# AirU_PoE_V2.net
KiCad netlist of a schematic drawn in EAGLE
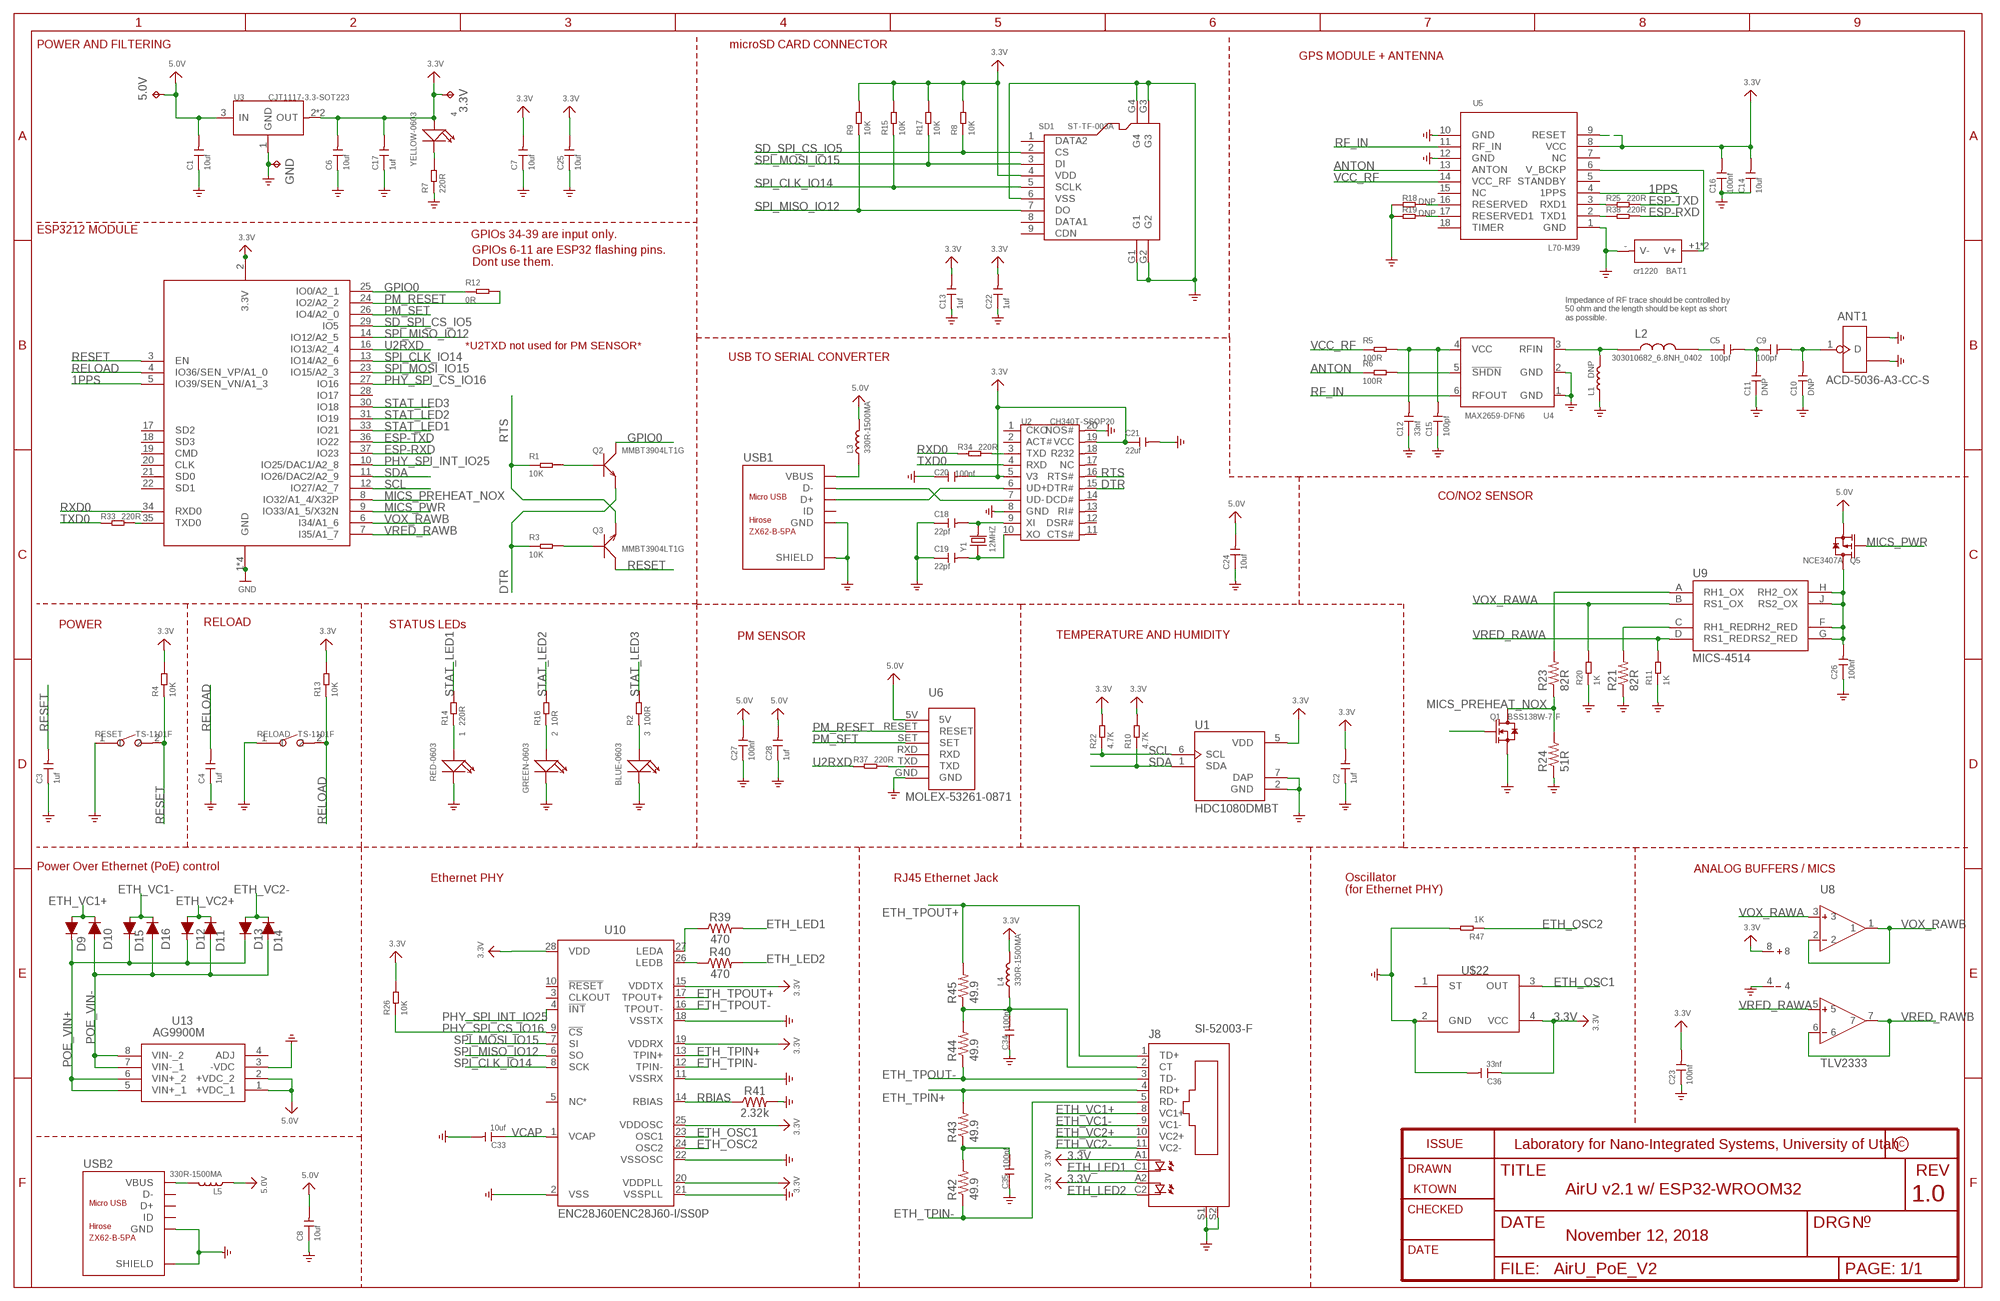
[diagram p0: schematic, sheet 1]

(export (version "E")
  (design (tool "Eeschema 10.0.6"))
  (components
    (comp (ref "1")
      (value "RED-0603")
      (footprint "eagle-import:LED-0603")
      (fields (field (name "MPN") "19-217-R6C-AL1M2VY-3T"))
      (libsource (lib "eagle-import") (part "LED-SMD-RED-DIFFUSED(0603)"))
    )
    (comp (ref "2")
      (value "GREEN-0603")
      (footprint "eagle-import:LED-0603")
      (fields (field (name "MPN") "19-217-G7C-AN1P2-3T"))
      (libsource (lib "eagle-import") (part "SMD-LED-CLEAR-GREEN(0603)"))
    )
    (comp (ref "3")
      (value "BLUE-0603")
      (footprint "eagle-import:LED-0603")
      (fields (field (name "MPN") "19-217-BHC-ZL1M2RY-3T"))
      (libsource (lib "eagle-import") (part "SMD-LED-CLEAR-BLUE(0603)"))
    )
    (comp (ref "3.3V")
      (value "TPTP20SQ")
      (footprint "eagle-import:TP20SQ")
      (libsource (lib "eagle-import") (part "TPTP20SQ"))
    )
    (comp (ref "4")
      (value "YELLOW-0603")
      (footprint "eagle-import:LED-0603")
      (fields (field (name "MPN") "19-217-Y5C-AM1N1VY-3T"))
      (libsource (lib "eagle-import") (part "SMD-LED-CLEAR-YELLOW(0603)"))
    )
    (comp (ref "5.0V")
      (value "TPTP20SQ")
      (footprint "eagle-import:TP20SQ")
      (libsource (lib "eagle-import") (part "TPTP20SQ"))
    )
    (comp (ref "ANT1")
      (value "ACD-5036-A3-CC-S")
      (footprint "eagle-import:ANT3-SMD-5.2X3.7X0.7MM")
      (libsource (lib "eagle-import") (part "ANTENNA-ACD5036"))
    )
    (comp (ref "BAT1")
      (value "cr1220")
      (footprint "eagle-import:BAT2P-13.5-CR1220")
      (libsource (lib "eagle-import") (part "DIP-BATTERY-CELL-HOLDER(1220)"))
    )
    (comp (ref "C1")
      (value "10uf")
      (footprint "eagle-import:C0603")
      (fields (field (name "MPN") "CC0603KRX5R6BB106"))
      (libsource (lib "eagle-import") (part "CERAMIC-10UF-10V-10%-X5R(0603)"))
    )
    (comp (ref "C2")
      (value "1uf")
      (footprint "eagle-import:C0603")
      (fields (field (name "MPN") "CC0603KRX7R8BB105"))
      (libsource (lib "eagle-import") (part "CERAMIC-1UF-25V-10%-X7R(0603)"))
    )
    (comp (ref "C3")
      (value "1uf")
      (footprint "eagle-import:C0603")
      (fields (field (name "MPN") "CC0603KRX7R8BB105"))
      (libsource (lib "eagle-import") (part "CERAMIC-1UF-25V-10%-X7R(0603)"))
    )
    (comp (ref "C4")
      (value "1uf")
      (footprint "eagle-import:C0603")
      (fields (field (name "MPN") "CC0603KRX7R8BB105"))
      (libsource (lib "eagle-import") (part "CERAMIC-1UF-25V-10%-X7R(0603)"))
    )
    (comp (ref "C5")
      (value "100pf")
      (footprint "eagle-import:C0603")
      (fields (field (name "MPN") "CC0603JRNPO9BN101"))
      (libsource (lib "eagle-import") (part "CERAMIC-100PF-50V-5%-NPO(0603)"))
    )
    (comp (ref "C6")
      (value "10uf")
      (footprint "eagle-import:C0603")
      (fields (field (name "MPN") "CC0603KRX5R6BB106"))
      (libsource (lib "eagle-import") (part "CERAMIC-10UF-10V-10%-X5R(0603)"))
    )
    (comp (ref "C7")
      (value "10uf")
      (footprint "eagle-import:C0603")
      (fields (field (name "MPN") "CC0603KRX5R6BB106"))
      (libsource (lib "eagle-import") (part "CERAMIC-10UF-10V-10%-X5R(0603)"))
    )
    (comp (ref "C8")
      (value "10uf")
      (footprint "eagle-import:C0603")
      (fields (field (name "MPN") "CC0603KRX5R6BB106"))
      (libsource (lib "eagle-import") (part "CERAMIC-10UF-10V-10%-X5R(0603)"))
    )
    (comp (ref "C9")
      (value "100pf")
      (footprint "eagle-import:C0603")
      (fields (field (name "MPN") "CC0603JRNPO9BN101"))
      (libsource (lib "eagle-import") (part "CERAMIC-100PF-50V-5%-NPO(0603)"))
    )
    (comp (ref "C10")
      (value "DNP")
      (footprint "eagle-import:C0603")
      (fields (field (name "MPN") "CC0603JRNPO9BN101"))
      (libsource (lib "eagle-import") (part "CERAMIC-100PF-50V-5%-NPO(0603)"))
    )
    (comp (ref "C11")
      (value "DNP")
      (footprint "eagle-import:C0603")
      (fields (field (name "MPN") "CC0603JRNPO9BN101"))
      (libsource (lib "eagle-import") (part "CERAMIC-100PF-50V-5%-NPO(0603)"))
    )
    (comp (ref "C12")
      (value "33nf")
      (footprint "eagle-import:C0603")
      (fields (field (name "MPN") "CC0603KRX7R9BB333"))
      (libsource (lib "eagle-import") (part "CERAMIC-33NF-50V-10%-X7R(0603)"))
    )
    (comp (ref "C13")
      (value "1uf")
      (footprint "eagle-import:C0603")
      (fields (field (name "MPN") "CC0603KRX7R8BB105"))
      (libsource (lib "eagle-import") (part "CERAMIC-1UF-25V-10%-X7R(0603)"))
    )
    (comp (ref "C14")
      (value "10uf")
      (footprint "eagle-import:C0603")
      (fields (field (name "MPN") "CC0603KRX5R6BB106"))
      (libsource (lib "eagle-import") (part "CERAMIC-10UF-10V-10%-X5R(0603)"))
    )
    (comp (ref "C15")
      (value "100pf")
      (footprint "eagle-import:C0603")
      (fields (field (name "MPN") "CC0603JRNPO9BN101"))
      (libsource (lib "eagle-import") (part "CERAMIC-100PF-50V-5%-NPO(0603)"))
    )
    (comp (ref "C16")
      (value "100nf")
      (footprint "eagle-import:C0603")
      (fields (field (name "MPN") "CC0603KRX7R9BB104"))
      (libsource (lib "eagle-import") (part "CERAMIC-100NF-50V-10%-X7R(0603)"))
    )
    (comp (ref "C17")
      (value "1uf")
      (footprint "eagle-import:C0603")
      (fields (field (name "MPN") "CC0603KRX7R8BB105"))
      (libsource (lib "eagle-import") (part "CERAMIC-1UF-25V-10%-X7R(0603)"))
    )
    (comp (ref "C18")
      (value "22pf")
      (footprint "eagle-import:C0603")
      (fields (field (name "MPN") "CC0603JRNPO9BN220"))
      (libsource (lib "eagle-import") (part "CERAMIC-22PF-50V-5%-NPO(0603)"))
    )
    (comp (ref "C19")
      (value "22pf")
      (footprint "eagle-import:C0603")
      (fields (field (name "MPN") "CC0603JRNPO9BN220"))
      (libsource (lib "eagle-import") (part "CERAMIC-22PF-50V-5%-NPO(0603)"))
    )
    (comp (ref "C20")
      (value "100nf")
      (footprint "eagle-import:C0603")
      (fields (field (name "MPN") "CC0603KRX7R9BB104"))
      (libsource (lib "eagle-import") (part "CERAMIC-100NF-50V-10%-X7R(0603)"))
    )
    (comp (ref "C21")
      (value "22uf")
      (footprint "eagle-import:C0805")
      (fields (field (name "MPN") "CC0805MKX5R5BB226"))
      (libsource (lib "eagle-import") (part "CERAMIC-22UF-6.3V-20%-X5R(0805)"))
    )
    (comp (ref "C22")
      (value "1uf")
      (footprint "eagle-import:C0603")
      (fields (field (name "MPN") "CC0603KRX7R8BB105"))
      (libsource (lib "eagle-import") (part "CERAMIC-1UF-25V-10%-X7R(0603)"))
    )
    (comp (ref "C23")
      (value "100nf")
      (footprint "eagle-import:C0603")
      (fields (field (name "MPN") "CC0603KRX7R9BB104"))
      (libsource (lib "eagle-import") (part "CERAMIC-100NF-50V-10%-X7R(0603)"))
    )
    (comp (ref "C24")
      (value "10uf")
      (footprint "eagle-import:C0603")
      (fields (field (name "MPN") "CC0603KRX5R6BB106"))
      (libsource (lib "eagle-import") (part "CERAMIC-10UF-10V-10%-X5R(0603)"))
    )
    (comp (ref "C25")
      (value "10uf")
      (footprint "eagle-import:C0603")
      (fields (field (name "MPN") "CC0603KRX5R6BB106"))
      (libsource (lib "eagle-import") (part "CERAMIC-10UF-10V-10%-X5R(0603)"))
    )
    (comp (ref "C26")
      (value "100nf")
      (footprint "eagle-import:C0603")
      (fields (field (name "MPN") "CC0603KRX7R9BB104"))
      (libsource (lib "eagle-import") (part "CERAMIC-100NF-50V-10%-X7R(0603)"))
    )
    (comp (ref "C27")
      (value "100nf")
      (footprint "eagle-import:C0603")
      (fields (field (name "MPN") "CC0603KRX7R9BB104"))
      (libsource (lib "eagle-import") (part "CERAMIC-100NF-50V-10%-X7R(0603)"))
    )
    (comp (ref "C28")
      (value "1uf")
      (footprint "eagle-import:C0603")
      (fields (field (name "MPN") "CC0603KRX7R8BB105"))
      (libsource (lib "eagle-import") (part "CERAMIC-1UF-25V-10%-X7R(0603)"))
    )
    (comp (ref "C33")
      (value "10uf")
      (footprint "eagle-import:C0603")
      (fields (field (name "MPN") "CC0603KRX5R6BB106"))
      (libsource (lib "eagle-import") (part "CERAMIC-10UF-10V-10%-X5R(0603)"))
    )
    (comp (ref "C34")
      (value "100nf")
      (footprint "eagle-import:C0603")
      (fields (field (name "MPN") "CC0603KRX7R9BB104"))
      (libsource (lib "eagle-import") (part "CERAMIC-100NF-50V-10%-X7R(0603)"))
    )
    (comp (ref "C35")
      (value "100nf")
      (footprint "eagle-import:C0603")
      (fields (field (name "MPN") "CC0603KRX7R9BB104"))
      (libsource (lib "eagle-import") (part "CERAMIC-100NF-50V-10%-X7R(0603)"))
    )
    (comp (ref "C36")
      (value "33nf")
      (footprint "eagle-import:C0603")
      (fields (field (name "MPN") "CC0603KRX7R9BB333"))
      (libsource (lib "eagle-import") (part "CERAMIC-33NF-50V-10%-X7R(0603)"))
    )
    (comp (ref "D9")
      (value "250mA/100V")
      (footprint "eagle-import:SOD-323")
      (libsource (lib "eagle-import") (part "DIODE-BAS16J"))
    )
    (comp (ref "D10")
      (value "250mA/100V")
      (footprint "eagle-import:SOD-323")
      (libsource (lib "eagle-import") (part "DIODE-BAS16J"))
    )
    (comp (ref "D11")
      (value "250mA/100V")
      (footprint "eagle-import:SOD-323")
      (libsource (lib "eagle-import") (part "DIODE-BAS16J"))
    )
    (comp (ref "D12")
      (value "250mA/100V")
      (footprint "eagle-import:SOD-323")
      (libsource (lib "eagle-import") (part "DIODE-BAS16J"))
    )
    (comp (ref "D13")
      (value "250mA/100V")
      (footprint "eagle-import:SOD-323")
      (libsource (lib "eagle-import") (part "DIODE-BAS16J"))
    )
    (comp (ref "D14")
      (value "250mA/100V")
      (footprint "eagle-import:SOD-323")
      (libsource (lib "eagle-import") (part "DIODE-BAS16J"))
    )
    (comp (ref "D15")
      (value "250mA/100V")
      (footprint "eagle-import:SOD-323")
      (libsource (lib "eagle-import") (part "DIODE-BAS16J"))
    )
    (comp (ref "D16")
      (value "250mA/100V")
      (footprint "eagle-import:SOD-323")
      (libsource (lib "eagle-import") (part "DIODE-BAS16J"))
    )
    (comp (ref "GND")
      (value "TPTP20SQ")
      (footprint "eagle-import:TP20SQ")
      (libsource (lib "eagle-import") (part "TPTP20SQ"))
    )
    (comp (ref "J8")
      (value "SI-52003-F")
      (footprint "eagle-import:SI-52003-F")
      (fields (field (name "MF") "Stewart Connector"))
      (libsource (lib "eagle-import") (part "SI-52003-F"))
    )
    (comp (ref "L1")
      (value "DNP")
      (footprint "eagle-import:L0201")
      (libsource (lib "eagle-import") (part "INDUCTOR/FERRITE-BEAD-0201"))
    )
    (comp (ref "L2")
      (value "303010682_6.8NH_0402")
      (footprint "eagle-import:L0402")
      (libsource (lib "eagle-import") (part "303010682_6.8NH_0402"))
    )
    (comp (ref "L3")
      (value "330R-1500MA")
      (footprint "eagle-import:L0805")
      (fields (field (name "MPN") "BLM21PG331SN1D"))
      (libsource (lib "eagle-import") (part "SMD-FERRITE-BEAD-330R-1500MA(0805)'0805'"))
    )
    (comp (ref "L4")
      (value "330R-1500MA")
      (footprint "eagle-import:L0805")
      (fields (field (name "MPN") "BLM21PG331SN1D"))
      (libsource (lib "eagle-import") (part "SMD-FERRITE-BEAD-330R-1500MA(0805)'0805'"))
    )
    (comp (ref "L5")
      (value "330R-1500MA")
      (footprint "eagle-import:L0805")
      (fields (field (name "MPN") "BLM21PG331SN1D"))
      (libsource (lib "eagle-import") (part "SMD-FERRITE-BEAD-330R-1500MA(0805)'0805'"))
    )
    (comp (ref "Q1")
      (value "BSS138W-7-F")
      (footprint "eagle-import:SOT-23")
      (libsource (lib "eagle-import") (part "SMD-MOSFET-N-CH-50V-200MA-BSS138W-7-F(SOT-23)"))
    )
    (comp (ref "Q2")
      (value "MMBT3904LT1G")
      (footprint "eagle-import:SOT-23")
      (libsource (lib "eagle-import") (part "SMD-TRANSISTORS-NPN-40V-200MA-MMBT3904LT1G(SOT-23)"))
    )
    (comp (ref "Q3")
      (value "MMBT3904LT1G")
      (footprint "eagle-import:SOT-23")
      (libsource (lib "eagle-import") (part "SMD-TRANSISTORS-NPN-40V-200MA-MMBT3904LT1G(SOT-23)"))
    )
    (comp (ref "Q5")
      (value "NCE3407A")
      (footprint "eagle-import:SOT-23")
      (libsource (lib "eagle-import") (part "SMD-MOSFET-P-CH-VDC=30V-ID=4.3A-NCE3407A(SOT-23)"))
    )
    (comp (ref "R1")
      (value "10K")
      (footprint "eagle-import:R0603")
      (fields (field (name "MPN") "RC0603FR-0710KL"))
      (libsource (lib "eagle-import") (part "SMD-RES-10K-1%-1/10W(0603)"))
    )
    (comp (ref "R2")
      (value "100R")
      (footprint "eagle-import:R0603")
      (fields (field (name "MPN") "RC0603JR-07100RL"))
      (libsource (lib "eagle-import") (part "SMD-RES-100R-5%-1/10W(0603)"))
    )
    (comp (ref "R3")
      (value "10K")
      (footprint "eagle-import:R0603")
      (fields (field (name "MPN") "RC0603FR-0710KL"))
      (libsource (lib "eagle-import") (part "SMD-RES-10K-1%-1/10W(0603)"))
    )
    (comp (ref "R4")
      (value "10K")
      (footprint "eagle-import:R0603")
      (fields (field (name "MPN") "RC0603FR-0710KL"))
      (libsource (lib "eagle-import") (part "SMD-RES-10K-1%-1/10W(0603)"))
    )
    (comp (ref "R5")
      (value "100R")
      (footprint "eagle-import:R0603")
      (fields (field (name "MPN") "RC0603JR-07100RL"))
      (libsource (lib "eagle-import") (part "SMD-RES-100R-5%-1/10W(0603)"))
    )
    (comp (ref "R6")
      (value "100R")
      (footprint "eagle-import:R0603")
      (fields (field (name "MPN") "RC0603JR-07100RL"))
      (libsource (lib "eagle-import") (part "SMD-RES-100R-5%-1/10W(0603)"))
    )
    (comp (ref "R7")
      (value "220R")
      (footprint "eagle-import:R0603")
      (fields (field (name "MPN") "RC0603JR-07220RL"))
      (libsource (lib "eagle-import") (part "SMD-RES-220R-5%-1/10W(0603)"))
    )
    (comp (ref "R8")
      (value "10K")
      (footprint "eagle-import:R0603")
      (fields (field (name "MPN") "RC0603FR-0710KL"))
      (libsource (lib "eagle-import") (part "SMD-RES-10K-1%-1/10W(0603)"))
    )
    (comp (ref "R9")
      (value "10K")
      (footprint "eagle-import:R0603")
      (fields (field (name "MPN") "RC0603FR-0710KL"))
      (libsource (lib "eagle-import") (part "SMD-RES-10K-1%-1/10W(0603)"))
    )
    (comp (ref "R10")
      (value "4.7K")
      (footprint "eagle-import:R0603")
      (fields (field (name "MPN") "RC0603JR-074K7L"))
      (libsource (lib "eagle-import") (part "SMD-RES-4.7K-5%-1/10W(0603)"))
    )
    (comp (ref "R11")
      (value "1K")
      (footprint "eagle-import:R0603")
      (fields (field (name "MPN") "RC0603FR-071KL"))
      (libsource (lib "eagle-import") (part "SMD-RES-1K-1%-1/10W(0603)"))
    )
    (comp (ref "R12")
      (value "0R")
      (footprint "eagle-import:R0603")
      (fields (field (name "MPN") "RC0603JR-070RL"))
      (libsource (lib "eagle-import") (part "SMD-RES-0R-5%-1/10W(0603)"))
    )
    (comp (ref "R13")
      (value "10K")
      (footprint "eagle-import:R0603")
      (fields (field (name "MPN") "RC0603FR-0710KL"))
      (libsource (lib "eagle-import") (part "SMD-RES-10K-1%-1/10W(0603)"))
    )
    (comp (ref "R14")
      (value "220R")
      (footprint "eagle-import:R0603")
      (fields (field (name "MPN") "RC0603JR-07220RL"))
      (libsource (lib "eagle-import") (part "SMD-RES-220R-5%-1/10W(0603)"))
    )
    (comp (ref "R15")
      (value "10K")
      (footprint "eagle-import:R0603")
      (fields (field (name "MPN") "RC0603FR-0710KL"))
      (libsource (lib "eagle-import") (part "SMD-RES-10K-1%-1/10W(0603)"))
    )
    (comp (ref "R16")
      (value "10R")
      (footprint "eagle-import:R0603")
      (fields (field (name "MPN") "RC0603JR-0710RL"))
      (libsource (lib "eagle-import") (part "SMD-RES-10R-5%-1/10W(0603)"))
    )
    (comp (ref "R17")
      (value "10K")
      (footprint "eagle-import:R0603")
      (fields (field (name "MPN") "RC0603FR-0710KL"))
      (libsource (lib "eagle-import") (part "SMD-RES-10K-1%-1/10W(0603)"))
    )
    (comp (ref "R18")
      (value "DNP")
      (footprint "eagle-import:R0603")
      (fields (field (name "MPN") "RC0603FR-0710KL"))
      (libsource (lib "eagle-import") (part "SMD-RES-10K-1%-1/10W(0603)"))
    )
    (comp (ref "R19")
      (value "DNP")
      (footprint "eagle-import:R0603")
      (fields (field (name "MPN") "RC0603FR-0710KL"))
      (libsource (lib "eagle-import") (part "SMD-RES-10K-1%-1/10W(0603)"))
    )
    (comp (ref "R20")
      (value "1K")
      (footprint "eagle-import:R0603")
      (fields (field (name "MPN") "RC0603FR-071KL"))
      (libsource (lib "eagle-import") (part "SMD-RES-1K-1%-1/10W(0603)"))
    )
    (comp (ref "R21")
      (value "82R")
      (footprint "eagle-import:R0603")
      (libsource (lib "eagle-import") (part "rcl_334_R-US_R0603"))
    )
    (comp (ref "R22")
      (value "4.7K")
      (footprint "eagle-import:R0603")
      (fields (field (name "MPN") "RC0603JR-074K7L"))
      (libsource (lib "eagle-import") (part "SMD-RES-4.7K-5%-1/10W(0603)"))
    )
    (comp (ref "R23")
      (value "82R")
      (footprint "eagle-import:R0603")
      (libsource (lib "eagle-import") (part "rcl_334_R-US_R0603"))
    )
    (comp (ref "R24")
      (value "51R")
      (footprint "eagle-import:R0603")
      (libsource (lib "eagle-import") (part "rcl_334_R-US_R0603"))
    )
    (comp (ref "R25")
      (value "220R")
      (footprint "eagle-import:R0603")
      (fields (field (name "MPN") "RC0603JR-07220RL"))
      (libsource (lib "eagle-import") (part "SMD-RES-220R-5%-1/10W(0603)"))
    )
    (comp (ref "R26")
      (value "10K")
      (footprint "eagle-import:R0603")
      (fields (field (name "MPN") "RC0603FR-0710KL"))
      (libsource (lib "eagle-import") (part "SMD-RES-10K-1%-1/10W(0603)"))
    )
    (comp (ref "R33")
      (value "220R")
      (footprint "eagle-import:R0603")
      (fields (field (name "MPN") "RC0603JR-07220RL"))
      (libsource (lib "eagle-import") (part "SMD-RES-220R-5%-1/10W(0603)"))
    )
    (comp (ref "R34")
      (value "220R")
      (footprint "eagle-import:R0603")
      (fields (field (name "MPN") "RC0603JR-07220RL"))
      (libsource (lib "eagle-import") (part "SMD-RES-220R-5%-1/10W(0603)"))
    )
    (comp (ref "R37")
      (value "220R")
      (footprint "eagle-import:R0603")
      (fields (field (name "MPN") "RC0603JR-07220RL"))
      (libsource (lib "eagle-import") (part "SMD-RES-220R-5%-1/10W(0603)"))
    )
    (comp (ref "R38")
      (value "220R")
      (footprint "eagle-import:R0603")
      (fields (field (name "MPN") "RC0603JR-07220RL"))
      (libsource (lib "eagle-import") (part "SMD-RES-220R-5%-1/10W(0603)"))
    )
    (comp (ref "R39")
      (value "470")
      (footprint "eagle-import:0603")
      (libsource (lib "eagle-import") (part "470OHM-0603-1/10W-1%"))
    )
    (comp (ref "R40")
      (value "470")
      (footprint "eagle-import:0603")
      (libsource (lib "eagle-import") (part "470OHM-0603-1/10W-1%"))
    )
    (comp (ref "R41")
      (value "2.32k")
      (footprint "eagle-import:0603")
      (libsource (lib "eagle-import") (part "2.2KOHM-0603-1/10W-1%"))
    )
    (comp (ref "R42")
      (value "49.9")
      (footprint "eagle-import:M0805")
      (libsource (lib "eagle-import") (part "R-US_M0805"))
    )
    (comp (ref "R43")
      (value "49.9")
      (footprint "eagle-import:M0805")
      (libsource (lib "eagle-import") (part "R-US_M0805"))
    )
    (comp (ref "R44")
      (value "49.9")
      (footprint "eagle-import:M0805")
      (libsource (lib "eagle-import") (part "R-US_M0805"))
    )
    (comp (ref "R45")
      (value "49.9")
      (footprint "eagle-import:M0805")
      (libsource (lib "eagle-import") (part "R-US_M0805"))
    )
    (comp (ref "R47")
      (value "1K")
      (footprint "eagle-import:R0603")
      (fields (field (name "MPN") "RC0603FR-071KL"))
      (libsource (lib "eagle-import") (part "SMD-RES-1K-1%-1/10W(0603)"))
    )
    (comp (ref "RELOAD")
      (value "TS-1101F")
      (footprint "eagle-import:SW2-5.0-6.0X3.0X4.3MM")
      (libsource (lib "eagle-import") (part "DIP-BUTTON(2P-6.0X3.0X4.3MM)-TS-1101F"))
    )
    (comp (ref "RESET")
      (value "TS-1101F")
      (footprint "eagle-import:SW2-5.0-6.0X3.0X4.3MM")
      (libsource (lib "eagle-import") (part "DIP-BUTTON(2P-6.0X3.0X4.3MM)-TS-1101F"))
    )
    (comp (ref "SD1")
      (value "ST-TF-003A")
      (footprint "eagle-import:MICRO-SD9+4P-SMD-16.1X14.5X1.85MM")
      (libsource (lib "eagle-import") (part "MICRO-SD-CARD-SOCKET-9P(ST-TF-003A)"))
    )
    (comp (ref "U$22")
      (value "SPXO25MHZ7050-4P")
      (footprint "eagle-import:DFN700X500X150-4N")
      (libsource (lib "eagle-import") (part "SPXO25MHZ7050-4P"))
    )
    (comp (ref "U1")
      (value "HDC1080DMBT")
      (footprint "eagle-import:SON100P300X300X80-7N")
      (fields (field (name "DIGI-KEY_PART_NUMBER") "296-43864-1-ND") (field (name "MF") "Texas Instruments"))
      (libsource (lib "eagle-import") (part "HDC1080DMBT"))
    )
    (comp (ref "U2")
      (value "CH340T-SSOP20")
      (footprint "eagle-import:SSOP20-0.65-7.6X5.2MM")
      (fields (field (name "MPN") "CH340T"))
      (libsource (lib "eagle-import") (part "INTERFACE-CH340T(SSOP20)"))
    )
    (comp (ref "U3")
      (value "CJT1117-3.3-SOT223")
      (footprint "eagle-import:SOT-223")
      (fields (field (name "MPN") "CJT1117-3.3"))
      (libsource (lib "eagle-import") (part "PMIC-CJT1117-3.3(SOT223)"))
    )
    (comp (ref "U4")
      (value "MAX2659-DFN6")
      (footprint "eagle-import:DFN6-0.5-1.5X1.2X0.72MM")
      (fields (field (name "MPN") "MAX2659"))
      (libsource (lib "eagle-import") (part "AMPLIFIER-MAX2659"))
    )
    (comp (ref "U5")
      (value "L70-M39")
      (footprint "eagle-import:LGA18-1.1-9.7X10.1X2.5MM")
      (fields (field (name "MPN") "L70"))
      (libsource (lib "eagle-import") (part "MOUDLE-GPS-L70-HARDWARE"))
    )
    (comp (ref "U6")
      (value "MOLEX-53261-0871")
      (footprint "eagle-import:MOLEX-53261-0871")
      (libsource (lib "eagle-import") (part "MOLEX-53261-0871"))
    )
    (comp (ref "U7")
      (value "ESP32_WROOM32_SKINNY")
      (footprint "eagle-import:WROOM32_SKINNY")
      (libsource (lib "eagle-import") (part "ESP32_WROOM32_SKINNY"))
    )
    (comp (ref "U8")
      (value "TLV2333")
      (footprint "eagle-import:TLV2333")
      (libsource (lib "eagle-import") (part "TLV2333"))
    )
    (comp (ref "U9")
      (value "MICS-4514")
      (footprint "eagle-import:MICS_10-SMD")
      (fields (field (name "MF") "Amphenol"))
      (libsource (lib "eagle-import") (part "MICS-4514"))
    )
    (comp (ref "U10")
      (value "ENC28J60ENC28J60-I/SS0P")
      (footprint "eagle-import:SOP65P780X200-28")
      (libsource (lib "eagle-import") (part "ENC28J60ENC28J60-I/SS0P"))
    )
    (comp (ref "U13")
      (value "AG9900M")
      (footprint "eagle-import:AG9900M")
      (fields (field (name "MANUFACTURER_PART_NUMBER") "Ag9900M"))
      (libsource (lib "eagle-import") (part "AG9900M"))
    )
    (comp (ref "USB1")
      (value "ZX62-B-5PA")
      (footprint "eagle-import:MICRO-USB5+6P-SMD-0.65-AB")
      (libsource (lib "eagle-import") (part "MICRO-USB-SMD(ZX62-B-5PA)"))
    )
    (comp (ref "USB2")
      (value "ZX62-B-5PA")
      (footprint "eagle-import:MICRO-USB5+6P-SMD-0.65-AB")
      (libsource (lib "eagle-import") (part "MICRO-USB-SMD(ZX62-B-5PA)"))
    )
    (comp (ref "Y1")
      (value "12MHZ")
      (footprint "eagle-import:X2-SMD-5.0X3.2X1.3MM")
      (fields (field (name "MPN") "5032/2P"))
      (libsource (lib "eagle-import") (part "SMD-CRYSTAL-12MHZ-20PF-20PPM-40R(2P-5.0X3.2MM)"))
    )
  )
  (nets
    (net (code "1") (name "/1PPS") (class "Default")
      (node (ref "U5") (pin "4") (pinfunction "1PPS_4") (pintype "bidirectional"))
      (node (ref "U7") (pin "5") (pinfunction "IO39/SEN_VN/A1_3_5") (pintype "passive"))
    )
    (net (code "2") (name "/ANTON") (class "Default")
      (node (ref "R6") (pin "1") (pinfunction "1_1") (pintype "passive"))
      (node (ref "U5") (pin "13") (pinfunction "ANTON_13") (pintype "bidirectional"))
    )
    (net (code "3") (name "/DTR") (class "Default")
      (node (ref "Q2") (pin "2") (pinfunction "E_2") (pintype "passive"))
      (node (ref "R3") (pin "1") (pinfunction "1_1") (pintype "passive"))
      (node (ref "U2") (pin "15") (pinfunction "DTR#_15") (pintype "output"))
    )
    (net (code "4") (name "/ESP-RXD") (class "Default")
      (node (ref "R38") (pin "2") (pinfunction "2_2") (pintype "passive"))
      (node (ref "U7") (pin "37") (pinfunction "IO23_37") (pintype "bidirectional"))
    )
    (net (code "5") (name "/ESP-TXD") (class "Default")
      (node (ref "R25") (pin "2") (pinfunction "2_2") (pintype "passive"))
      (node (ref "U7") (pin "36") (pinfunction "IO22_36") (pintype "bidirectional"))
    )
    (net (code "6") (name "/ETH_LED1") (class "Default")
      (node (ref "J8") (pin "C1") (pinfunction "C1_C1") (pintype "passive"))
      (node (ref "R39") (pin "2") (pinfunction "2_2") (pintype "passive"))
    )
    (net (code "7") (name "/ETH_LED2") (class "Default")
      (node (ref "J8") (pin "C2") (pinfunction "C2_C2") (pintype "passive"))
      (node (ref "R40") (pin "2") (pinfunction "2_2") (pintype "passive"))
    )
    (net (code "8") (name "/ETH_OSC1") (class "Default")
      (node (ref "U$22") (pin "3") (pinfunction "OUT_3") (pintype "bidirectional"))
      (node (ref "U10") (pin "23") (pinfunction "OSC1_23") (pintype "input"))
    )
    (net (code "9") (name "/ETH_OSC2") (class "Default")
      (node (ref "R47") (pin "1") (pinfunction "1_1") (pintype "passive"))
      (node (ref "U10") (pin "24") (pinfunction "OSC2_24") (pintype "output"))
    )
    (net (code "10") (name "/ETH_TPIN+") (class "Default")
      (node (ref "J8") (pin "4") (pinfunction "RD+_4") (pintype "passive"))
      (node (ref "R43") (pin "2") (pinfunction "2_2") (pintype "passive"))
      (node (ref "U10") (pin "13") (pinfunction "TPIN+_13") (pintype "input"))
    )
    (net (code "11") (name "/ETH_TPIN-") (class "Default")
      (node (ref "J8") (pin "5") (pinfunction "RD-_5") (pintype "passive"))
      (node (ref "R42") (pin "1") (pinfunction "1_1") (pintype "passive"))
      (node (ref "U10") (pin "12") (pinfunction "TPIN-_12") (pintype "input"))
    )
    (net (code "12") (name "/ETH_TPOUT+") (class "Default")
      (node (ref "J8") (pin "1") (pinfunction "TD+_1") (pintype "passive"))
      (node (ref "R45") (pin "2") (pinfunction "2_2") (pintype "passive"))
      (node (ref "U10") (pin "17") (pinfunction "TPOUT+_17") (pintype "output"))
    )
    (net (code "13") (name "/ETH_TPOUT-") (class "Default")
      (node (ref "J8") (pin "3") (pinfunction "TD-_3") (pintype "passive"))
      (node (ref "R44") (pin "1") (pinfunction "1_1") (pintype "passive"))
      (node (ref "U10") (pin "16") (pinfunction "TPOUT-_16") (pintype "output"))
    )
    (net (code "14") (name "/ETH_VC1+") (class "Default")
      (node (ref "D10") (pin "C") (pinfunction "C_C") (pintype "passive"))
      (node (ref "D9") (pin "A") (pinfunction "A_A") (pintype "passive"))
      (node (ref "J8") (pin "8") (pinfunction "VC1+_8") (pintype "passive"))
    )
    (net (code "15") (name "/ETH_VC1-") (class "Default")
      (node (ref "D15") (pin "A") (pinfunction "A_A") (pintype "passive"))
      (node (ref "D16") (pin "C") (pinfunction "C_C") (pintype "passive"))
      (node (ref "J8") (pin "9") (pinfunction "VC1-_9") (pintype "passive"))
    )
    (net (code "16") (name "/ETH_VC2+") (class "Default")
      (node (ref "D11") (pin "C") (pinfunction "C_C") (pintype "passive"))
      (node (ref "D12") (pin "A") (pinfunction "A_A") (pintype "passive"))
      (node (ref "J8") (pin "10") (pinfunction "VC2+_10") (pintype "passive"))
    )
    (net (code "17") (name "/ETH_VC2-") (class "Default")
      (node (ref "D13") (pin "A") (pinfunction "A_A") (pintype "passive"))
      (node (ref "D14") (pin "C") (pinfunction "C_C") (pintype "passive"))
      (node (ref "J8") (pin "11") (pinfunction "VC2-_11") (pintype "bidirectional"))
    )
    (net (code "18") (name "/GPIO0") (class "Default")
      (node (ref "Q2") (pin "3") (pinfunction "C_3") (pintype "passive"))
      (node (ref "R12") (pin "1") (pinfunction "1_1") (pintype "passive"))
      (node (ref "U7") (pin "25") (pinfunction "IO0/A2_1_25") (pintype "bidirectional"))
    )
    (net (code "19") (name "/MICS_PREHEAT_NOX") (class "Default")
      (node (ref "Q1") (pin "1") (pinfunction "G_1") (pintype "passive"))
      (node (ref "U7") (pin "8") (pinfunction "IO32/A1_4/X32P_8") (pintype "bidirectional"))
    )
    (net (code "20") (name "/MICS_PWR") (class "Default")
      (node (ref "Q5") (pin "1") (pinfunction "G_1") (pintype "passive"))
      (node (ref "U7") (pin "9") (pinfunction "IO33/A1_5/X32N_9") (pintype "bidirectional"))
    )
    (net (code "21") (name "/PHY_SPI_CS_IO16") (class "Default")
      (node (ref "R26") (pin "1") (pinfunction "1_1") (pintype "passive"))
      (node (ref "U10") (pin "9") (pinfunction "~{CS}_9") (pintype "input"))
      (node (ref "U7") (pin "27") (pinfunction "IO16_27") (pintype "bidirectional"))
    )
    (net (code "22") (name "/PHY_SPI_INT_IO25") (class "Default")
      (node (ref "U10") (pin "4") (pinfunction "~{INT}_4") (pintype "output"))
      (node (ref "U7") (pin "10") (pinfunction "IO25/DAC1/A2_8_10") (pintype "bidirectional"))
    )
    (net (code "23") (name "/PM_RESET") (class "Default")
      (node (ref "R12") (pin "2") (pinfunction "2_2") (pintype "passive"))
      (node (ref "U6") (pin "RESET") (pinfunction "RESET_RESET") (pintype "bidirectional"))
      (node (ref "U7") (pin "24") (pinfunction "IO2/A2_2_24") (pintype "bidirectional"))
    )
    (net (code "24") (name "/PM_SET") (class "Default")
      (node (ref "U6") (pin "SET") (pinfunction "SET_SET") (pintype "bidirectional"))
      (node (ref "U7") (pin "26") (pinfunction "IO4/A2_0_26") (pintype "bidirectional"))
    )
    (net (code "25") (name "/POE_VIN+") (class "Default")
      (node (ref "D12") (pin "C") (pinfunction "C_C") (pintype "passive"))
      (node (ref "D13") (pin "C") (pinfunction "C_C") (pintype "passive"))
      (node (ref "D15") (pin "C") (pinfunction "C_C") (pintype "passive"))
      (node (ref "D9") (pin "C") (pinfunction "C_C") (pintype "passive"))
      (node (ref "U13") (pin "5") (pinfunction "VIN+_1_5") (pintype "bidirectional"))
      (node (ref "U13") (pin "6") (pinfunction "VIN+_2_6") (pintype "bidirectional"))
    )
    (net (code "26") (name "/POE_VIN-") (class "Default")
      (node (ref "D10") (pin "A") (pinfunction "A_A") (pintype "passive"))
      (node (ref "D11") (pin "A") (pinfunction "A_A") (pintype "passive"))
      (node (ref "D14") (pin "A") (pinfunction "A_A") (pintype "passive"))
      (node (ref "D16") (pin "A") (pinfunction "A_A") (pintype "passive"))
      (node (ref "U13") (pin "7") (pinfunction "VIN-_1_7") (pintype "bidirectional"))
      (node (ref "U13") (pin "8") (pinfunction "VIN-_2_8") (pintype "bidirectional"))
    )
    (net (code "27") (name "/RBIAS") (class "Default")
      (node (ref "R41") (pin "1") (pinfunction "1_1") (pintype "passive"))
      (node (ref "U10") (pin "14") (pinfunction "RBIAS_14") (pintype "input"))
    )
    (net (code "28") (name "/RELOAD") (class "Default")
      (node (ref "C4") (pin "2") (pinfunction "2_2") (pintype "passive"))
      (node (ref "R13") (pin "1") (pinfunction "1_1") (pintype "passive"))
      (node (ref "RELOAD") (pin "2") (pinfunction "2_2") (pintype "bidirectional"))
      (node (ref "U7") (pin "4") (pinfunction "IO36/SEN_VP/A1_0_4") (pintype "passive"))
    )
    (net (code "29") (name "/RESET") (class "Default")
      (node (ref "C3") (pin "2") (pinfunction "2_2") (pintype "passive"))
      (node (ref "Q3") (pin "3") (pinfunction "C_3") (pintype "passive"))
      (node (ref "R4") (pin "1") (pinfunction "1_1") (pintype "passive"))
      (node (ref "RESET") (pin "2") (pinfunction "2_2") (pintype "bidirectional"))
      (node (ref "U7") (pin "3") (pinfunction "EN_3") (pintype "input"))
    )
    (net (code "30") (name "/RF_IN") (class "Default")
      (node (ref "U4") (pin "6") (pinfunction "RFOUT_6") (pintype "bidirectional"))
      (node (ref "U5") (pin "11") (pinfunction "RF_IN_11") (pintype "bidirectional"))
    )
    (net (code "31") (name "/RTS") (class "Default")
      (node (ref "Q3") (pin "2") (pinfunction "E_2") (pintype "passive"))
      (node (ref "R1") (pin "1") (pinfunction "1_1") (pintype "passive"))
      (node (ref "U2") (pin "16") (pinfunction "RTS#_16") (pintype "output"))
    )
    (net (code "32") (name "/RXD0") (class "Default")
      (node (ref "R34") (pin "1") (pinfunction "1_1") (pintype "passive"))
      (node (ref "U7") (pin "34") (pinfunction "RXD0_34") (pintype "input"))
    )
    (net (code "33") (name "/SCL") (class "Default")
      (node (ref "R22") (pin "1") (pinfunction "1_1") (pintype "passive"))
      (node (ref "U1") (pin "6") (pinfunction "SCL_6") (pintype "input"))
      (node (ref "U7") (pin "12") (pinfunction "IO27/A2_7_12") (pintype "bidirectional"))
    )
    (net (code "34") (name "/SDA") (class "Default")
      (node (ref "R10") (pin "1") (pinfunction "1_1") (pintype "passive"))
      (node (ref "U1") (pin "1") (pinfunction "SDA_1") (pintype "bidirectional"))
      (node (ref "U7") (pin "11") (pinfunction "IO26/DAC2/A2_9_11") (pintype "bidirectional"))
    )
    (net (code "35") (name "/SD_SPI_CS_IO5") (class "Default")
      (node (ref "R8") (pin "1") (pinfunction "1_1") (pintype "passive"))
      (node (ref "SD1") (pin "2") (pinfunction "CS_2") (pintype "bidirectional"))
      (node (ref "U7") (pin "29") (pinfunction "IO5_29") (pintype "bidirectional"))
    )
    (net (code "36") (name "/SPI_CLK_IO14") (class "Default")
      (node (ref "R15") (pin "1") (pinfunction "1_1") (pintype "passive"))
      (node (ref "SD1") (pin "5") (pinfunction "SCLK_5") (pintype "bidirectional"))
      (node (ref "U10") (pin "8") (pinfunction "SCK_8") (pintype "input"))
      (node (ref "U7") (pin "13") (pinfunction "IO14/A2_6_13") (pintype "bidirectional"))
    )
    (net (code "37") (name "/SPI_MISO_IO12") (class "Default")
      (node (ref "R9") (pin "1") (pinfunction "1_1") (pintype "passive"))
      (node (ref "SD1") (pin "7") (pinfunction "DO_7") (pintype "bidirectional"))
      (node (ref "U10") (pin "6") (pinfunction "SO_6") (pintype "output"))
      (node (ref "U7") (pin "14") (pinfunction "IO12/A2_5_14") (pintype "bidirectional"))
    )
    (net (code "38") (name "/SPI_MOSI_IO15") (class "Default")
      (node (ref "R17") (pin "1") (pinfunction "1_1") (pintype "passive"))
      (node (ref "SD1") (pin "3") (pinfunction "DI_3") (pintype "bidirectional"))
      (node (ref "U10") (pin "7") (pinfunction "SI_7") (pintype "input"))
      (node (ref "U7") (pin "23") (pinfunction "IO15/A2_3_23") (pintype "bidirectional"))
    )
    (net (code "39") (name "/STAT_LED1") (class "Default")
      (node (ref "R14") (pin "2") (pinfunction "2_2") (pintype "passive"))
      (node (ref "U7") (pin "33") (pinfunction "IO21_33") (pintype "bidirectional"))
    )
    (net (code "40") (name "/STAT_LED2") (class "Default")
      (node (ref "R16") (pin "2") (pinfunction "2_2") (pintype "passive"))
      (node (ref "U7") (pin "31") (pinfunction "IO19_31") (pintype "bidirectional"))
    )
    (net (code "41") (name "/STAT_LED3") (class "Default")
      (node (ref "R2") (pin "2") (pinfunction "2_2") (pintype "passive"))
      (node (ref "U7") (pin "30") (pinfunction "IO18_30") (pintype "bidirectional"))
    )
    (net (code "42") (name "/TXD0") (class "Default")
      (node (ref "R33") (pin "1") (pinfunction "1_1") (pintype "passive"))
      (node (ref "U2") (pin "4") (pinfunction "RXD_4") (pintype "input"))
    )
    (net (code "43") (name "/U2RXD") (class "Default")
      (node (ref "R37") (pin "1") (pinfunction "1_1") (pintype "passive"))
      (node (ref "U7") (pin "16") (pinfunction "IO13/A2_4_16") (pintype "bidirectional"))
    )
    (net (code "44") (name "/VBUS") (class "Default")
      (node (ref "L3") (pin "1") (pinfunction "1_1") (pintype "passive"))
      (node (ref "L5") (pin "2") (pinfunction "2_2") (pintype "passive"))
      (node (ref "USB1") (pin "1") (pinfunction "VBUS_1") (pintype "power_in"))
      (node (ref "USB2") (pin "1") (pinfunction "VBUS_1") (pintype "power_in"))
    )
    (net (code "45") (name "/VCAP") (class "Default")
      (node (ref "C33") (pin "1") (pinfunction "1_1") (pintype "passive"))
      (node (ref "U10") (pin "1") (pinfunction "VCAP_1") (pintype "input"))
    )
    (net (code "46") (name "/VCC_RF") (class "Default")
      (node (ref "R5") (pin "1") (pinfunction "1_1") (pintype "passive"))
      (node (ref "U5") (pin "14") (pinfunction "VCC_RF_14") (pintype "power_in"))
    )
    (net (code "47") (name "/VOX_RAWA") (class "Default")
      (node (ref "R20") (pin "2") (pinfunction "2_2") (pintype "passive"))
      (node (ref "U8") (pin "3") (pinfunction "3_3") (pintype "bidirectional"))
      (node (ref "U9") (pin "B") (pinfunction "RS1_OX_B") (pintype "bidirectional"))
    )
    (net (code "48") (name "/VOX_RAWB") (class "Default")
      (node (ref "U7") (pin "6") (pinfunction "I34/A1_6_6") (pintype "bidirectional"))
      (node (ref "U8") (pin "1") (pinfunction "1_1") (pintype "bidirectional"))
      (node (ref "U8") (pin "2") (pinfunction "2_2") (pintype "bidirectional"))
    )
    (net (code "49") (name "/VRED_RAWA") (class "Default")
      (node (ref "R11") (pin "2") (pinfunction "2_2") (pintype "passive"))
      (node (ref "U8") (pin "5") (pinfunction "5_5") (pintype "bidirectional"))
      (node (ref "U9") (pin "D") (pinfunction "RS1_RED_D") (pintype "bidirectional"))
    )
    (net (code "50") (name "/VRED_RAWB") (class "Default")
      (node (ref "U7") (pin "7") (pinfunction "I35/A1_7_7") (pintype "bidirectional"))
      (node (ref "U8") (pin "6") (pinfunction "6_6") (pintype "bidirectional"))
      (node (ref "U8") (pin "7") (pinfunction "7_7") (pintype "bidirectional"))
    )
    (net (code "51") (name "3.3V") (class "Default")
      (node (ref "3.3V") (pin "TP") (pinfunction "TP_TP") (pintype "input"))
      (node (ref "4") (pin "+") (pinfunction "+_+") (pintype "passive"))
      (node (ref "C13") (pin "2") (pinfunction "2_2") (pintype "passive"))
      (node (ref "C14") (pin "2") (pinfunction "2_2") (pintype "passive"))
      (node (ref "C16") (pin "2") (pinfunction "2_2") (pintype "passive"))
      (node (ref "C17") (pin "2") (pinfunction "2_2") (pintype "passive"))
      (node (ref "C2") (pin "2") (pinfunction "2_2") (pintype "passive"))
      (node (ref "C20") (pin "2") (pinfunction "2_2") (pintype "passive"))
      (node (ref "C21") (pin "1") (pinfunction "1_1") (pintype "passive"))
      (node (ref "C22") (pin "2") (pinfunction "2_2") (pintype "passive"))
      (node (ref "C23") (pin "2") (pinfunction "2_2") (pintype "passive"))
      (node (ref "C25") (pin "2") (pinfunction "2_2") (pintype "passive"))
      (node (ref "C36") (pin "1") (pinfunction "1_1") (pintype "passive"))
      (node (ref "C6") (pin "2") (pinfunction "2_2") (pintype "passive"))
      (node (ref "C7") (pin "2") (pinfunction "2_2") (pintype "passive"))
      (node (ref "J8") (pin "A1") (pinfunction "A1_A1") (pintype "passive"))
      (node (ref "J8") (pin "A2") (pinfunction "A2_A2") (pintype "passive"))
      (node (ref "L4") (pin "2") (pinfunction "2_2") (pintype "passive"))
      (node (ref "R10") (pin "2") (pinfunction "2_2") (pintype "passive"))
      (node (ref "R13") (pin "2") (pinfunction "2_2") (pintype "passive"))
      (node (ref "R15") (pin "2") (pinfunction "2_2") (pintype "passive"))
      (node (ref "R17") (pin "2") (pinfunction "2_2") (pintype "passive"))
      (node (ref "R22") (pin "2") (pinfunction "2_2") (pintype "passive"))
      (node (ref "R26") (pin "2") (pinfunction "2_2") (pintype "passive"))
      (node (ref "R4") (pin "2") (pinfunction "2_2") (pintype "passive"))
      (node (ref "R8") (pin "2") (pinfunction "2_2") (pintype "passive"))
      (node (ref "R9") (pin "2") (pinfunction "2_2") (pintype "passive"))
      (node (ref "SD1") (pin "4") (pinfunction "VDD_4") (pintype "bidirectional"))
      (node (ref "U$22") (pin "4") (pinfunction "VCC_4") (pintype "bidirectional"))
      (node (ref "U1") (pin "5") (pinfunction "VDD_5") (pintype "power_in"))
      (node (ref "U10") (pin "15") (pinfunction "VDDTX_15") (pintype "input"))
      (node (ref "U10") (pin "19") (pinfunction "VDDRX_19") (pintype "input"))
      (node (ref "U10") (pin "20") (pinfunction "VDDPLL_20") (pintype "input"))
      (node (ref "U10") (pin "25") (pinfunction "VDDOSC_25") (pintype "input"))
      (node (ref "U10") (pin "28") (pinfunction "VDD_28") (pintype "input"))
      (node (ref "U2") (pin "19") (pinfunction "VCC_19") (pintype "power_in"))
      (node (ref "U2") (pin "5") (pinfunction "V3_5") (pintype "power_in"))
      (node (ref "U3") (pin "2") (pinfunction "OUT_2") (pintype "bidirectional"))
      (node (ref "U3") (pin "TER") (pinfunction "OUT_TER") (pintype "bidirectional"))
      (node (ref "U5") (pin "8") (pinfunction "VCC_8") (pintype "power_in"))
      (node (ref "U5") (pin "9") (pinfunction "RESET_9") (pintype "bidirectional"))
      (node (ref "U7") (pin "2") (pinfunction "3.3V_2") (pintype "passive"))
      (node (ref "U8") (pin "8") (pinfunction "8_8") (pintype "bidirectional"))
    )
    (net (code "52") (name "5.0V") (class "Default")
      (node (ref "5.0V") (pin "TP") (pinfunction "TP_TP") (pintype "input"))
      (node (ref "C1") (pin "2") (pinfunction "2_2") (pintype "passive"))
      (node (ref "C24") (pin "2") (pinfunction "2_2") (pintype "passive"))
      (node (ref "C27") (pin "2") (pinfunction "2_2") (pintype "passive"))
      (node (ref "C28") (pin "2") (pinfunction "2_2") (pintype "passive"))
      (node (ref "C8") (pin "2") (pinfunction "2_2") (pintype "passive"))
      (node (ref "L3") (pin "2") (pinfunction "2_2") (pintype "passive"))
      (node (ref "L5") (pin "1") (pinfunction "1_1") (pintype "passive"))
      (node (ref "Q5") (pin "2") (pinfunction "S_2") (pintype "passive"))
      (node (ref "U13") (pin "1") (pinfunction "+VDC_1_1") (pintype "bidirectional"))
      (node (ref "U13") (pin "2") (pinfunction "+VDC_2_2") (pintype "bidirectional"))
      (node (ref "U3") (pin "3") (pinfunction "IN_3") (pintype "bidirectional"))
      (node (ref "U6") (pin "5V") (pinfunction "5V_5V") (pintype "bidirectional"))
    )
    (net (code "53") (name "GND") (class "Default")
      (node (ref "1") (pin "-") (pinfunction "-_-") (pintype "passive"))
      (node (ref "2") (pin "-") (pinfunction "-_-") (pintype "passive"))
      (node (ref "3") (pin "-") (pinfunction "-_-") (pintype "passive"))
      (node (ref "ANT1") (pin "2") (pinfunction "GND1_2") (pintype "bidirectional"))
      (node (ref "ANT1") (pin "3") (pinfunction "GND2_3") (pintype "bidirectional"))
      (node (ref "BAT1") (pin "-") (pinfunction "V-_-") (pintype "bidirectional"))
      (node (ref "C1") (pin "1") (pinfunction "1_1") (pintype "passive"))
      (node (ref "C10") (pin "1") (pinfunction "1_1") (pintype "passive"))
      (node (ref "C11") (pin "1") (pinfunction "1_1") (pintype "passive"))
      (node (ref "C12") (pin "1") (pinfunction "1_1") (pintype "passive"))
      (node (ref "C13") (pin "1") (pinfunction "1_1") (pintype "passive"))
      (node (ref "C14") (pin "1") (pinfunction "1_1") (pintype "passive"))
      (node (ref "C15") (pin "1") (pinfunction "1_1") (pintype "passive"))
      (node (ref "C16") (pin "1") (pinfunction "1_1") (pintype "passive"))
      (node (ref "C17") (pin "1") (pinfunction "1_1") (pintype "passive"))
      (node (ref "C18") (pin "1") (pinfunction "1_1") (pintype "passive"))
      (node (ref "C19") (pin "1") (pinfunction "1_1") (pintype "passive"))
      (node (ref "C2") (pin "1") (pinfunction "1_1") (pintype "passive"))
      (node (ref "C20") (pin "1") (pinfunction "1_1") (pintype "passive"))
      (node (ref "C21") (pin "2") (pinfunction "2_2") (pintype "passive"))
      (node (ref "C22") (pin "1") (pinfunction "1_1") (pintype "passive"))
      (node (ref "C23") (pin "1") (pinfunction "1_1") (pintype "passive"))
      (node (ref "C24") (pin "1") (pinfunction "1_1") (pintype "passive"))
      (node (ref "C25") (pin "1") (pinfunction "1_1") (pintype "passive"))
      (node (ref "C26") (pin "1") (pinfunction "1_1") (pintype "passive"))
      (node (ref "C27") (pin "1") (pinfunction "1_1") (pintype "passive"))
      (node (ref "C28") (pin "1") (pinfunction "1_1") (pintype "passive"))
      (node (ref "C3") (pin "1") (pinfunction "1_1") (pintype "passive"))
      (node (ref "C33") (pin "2") (pinfunction "2_2") (pintype "passive"))
      (node (ref "C34") (pin "1") (pinfunction "1_1") (pintype "passive"))
      (node (ref "C35") (pin "1") (pinfunction "1_1") (pintype "passive"))
      (node (ref "C36") (pin "2") (pinfunction "2_2") (pintype "passive"))
      (node (ref "C4") (pin "1") (pinfunction "1_1") (pintype "passive"))
      (node (ref "C6") (pin "1") (pinfunction "1_1") (pintype "passive"))
      (node (ref "C7") (pin "1") (pinfunction "1_1") (pintype "passive"))
      (node (ref "C8") (pin "1") (pinfunction "1_1") (pintype "passive"))
      (node (ref "GND") (pin "TP") (pinfunction "TP_TP") (pintype "input"))
      (node (ref "J8") (pin "S1") (pinfunction "S1_S1") (pintype "passive"))
      (node (ref "J8") (pin "S2") (pinfunction "S2_S2") (pintype "passive"))
      (node (ref "L1") (pin "1") (pinfunction "1_1") (pintype "passive"))
      (node (ref "Q1") (pin "2") (pinfunction "S_2") (pintype "passive"))
      (node (ref "R11") (pin "1") (pinfunction "1_1") (pintype "passive"))
      (node (ref "R18") (pin "1") (pinfunction "1_1") (pintype "passive"))
      (node (ref "R19") (pin "1") (pinfunction "1_1") (pintype "passive"))
      (node (ref "R20") (pin "1") (pinfunction "1_1") (pintype "passive"))
      (node (ref "R21") (pin "1") (pinfunction "1_1") (pintype "passive"))
      (node (ref "R24") (pin "1") (pinfunction "1_1") (pintype "passive"))
      (node (ref "R41") (pin "2") (pinfunction "2_2") (pintype "passive"))
      (node (ref "R47") (pin "2") (pinfunction "2_2") (pintype "passive"))
      (node (ref "R7") (pin "1") (pinfunction "1_1") (pintype "passive"))
      (node (ref "RELOAD") (pin "1") (pinfunction "1_1") (pintype "bidirectional"))
      (node (ref "RESET") (pin "1") (pinfunction "1_1") (pintype "bidirectional"))
      (node (ref "SD1") (pin "6") (pinfunction "VSS_6") (pintype "bidirectional"))
      (node (ref "SD1") (pin "G1") (pinfunction "G1_G1") (pintype "bidirectional"))
      (node (ref "SD1") (pin "G2") (pinfunction "G2_G2") (pintype "bidirectional"))
      (node (ref "SD1") (pin "G3") (pinfunction "G3_G3") (pintype "bidirectional"))
      (node (ref "SD1") (pin "G4") (pinfunction "G4_G4") (pintype "bidirectional"))
      (node (ref "U$22") (pin "2") (pinfunction "GND_2") (pintype "bidirectional"))
      (node (ref "U1") (pin "2") (pinfunction "GND_2") (pintype "power_in"))
      (node (ref "U1") (pin "7") (pinfunction "DAP_7") (pintype "power_in"))
      (node (ref "U10") (pin "11") (pinfunction "VSSRX_11") (pintype "input"))
      (node (ref "U10") (pin "18") (pinfunction "VSSTX_18") (pintype "input"))
      (node (ref "U10") (pin "2") (pinfunction "VSS_2") (pintype "input"))
      (node (ref "U10") (pin "21") (pinfunction "VSSPLL_21") (pintype "input"))
      (node (ref "U10") (pin "22") (pinfunction "VSSOSC_22") (pintype "input"))
      (node (ref "U13") (pin "3") (pinfunction "-VDC_3") (pintype "bidirectional"))
      (node (ref "U2") (pin "20") (pinfunction "NOS#_20") (pintype "power_in"))
      (node (ref "U2") (pin "8") (pinfunction "GND_8") (pintype "power_in"))
      (node (ref "U3") (pin "1") (pinfunction "GND_1") (pintype "bidirectional"))
      (node (ref "U4") (pin "1") (pinfunction "GND_1") (pintype "power_in"))
      (node (ref "U4") (pin "2") (pinfunction "GND_2") (pintype "power_in"))
      (node (ref "U5") (pin "1") (pinfunction "GND_1") (pintype "power_in"))
      (node (ref "U5") (pin "10") (pinfunction "GND_10") (pintype "power_in"))
      (node (ref "U5") (pin "12") (pinfunction "GND_12") (pintype "bidirectional"))
      (node (ref "U6") (pin "GND") (pinfunction "GND_GND") (pintype "bidirectional"))
      (node (ref "U7") (pin "1") (pinfunction "GND_1") (pintype "passive"))
      (node (ref "U7") (pin "15") (pinfunction "GND_15") (pintype "passive"))
      (node (ref "U7") (pin "38") (pinfunction "GND_38") (pintype "passive"))
      (node (ref "U7") (pin "P$1") (pinfunction "GND_P$1") (pintype "passive"))
      (node (ref "U8") (pin "4") (pinfunction "4_4") (pintype "bidirectional"))
      (node (ref "USB1") (pin "5") (pinfunction "GND_5") (pintype "power_in"))
      (node (ref "USB1") (pin "P1") (pinfunction "SHIELD_P1") (pintype "power_in"))
      (node (ref "USB1") (pin "P2") (pinfunction "SHIELD_P2") (pintype "power_in"))
      (node (ref "USB1") (pin "P3_1") (pinfunction "SHIELD_P3_1") (pintype "power_in"))
      (node (ref "USB1") (pin "P3_2") (pinfunction "SHIELD_P3_2") (pintype "power_in"))
      (node (ref "USB1") (pin "P3_3") (pinfunction "SHIELD_P3_3") (pintype "power_in"))
      (node (ref "USB1") (pin "P4_1") (pinfunction "SHIELD_P4_1") (pintype "power_in"))
      (node (ref "USB1") (pin "P4_2") (pinfunction "SHIELD_P4_2") (pintype "power_in"))
      (node (ref "USB1") (pin "P4_3") (pinfunction "SHIELD_P4_3") (pintype "power_in"))
      (node (ref "USB1") (pin "P5") (pinfunction "SHIELD_P5") (pintype "power_in"))
      (node (ref "USB1") (pin "P6") (pinfunction "SHIELD_P6") (pintype "power_in"))
      (node (ref "USB2") (pin "5") (pinfunction "GND_5") (pintype "power_in"))
      (node (ref "USB2") (pin "P1") (pinfunction "SHIELD_P1") (pintype "power_in"))
      (node (ref "USB2") (pin "P2") (pinfunction "SHIELD_P2") (pintype "power_in"))
      (node (ref "USB2") (pin "P3_1") (pinfunction "SHIELD_P3_1") (pintype "power_in"))
      (node (ref "USB2") (pin "P3_2") (pinfunction "SHIELD_P3_2") (pintype "power_in"))
      (node (ref "USB2") (pin "P3_3") (pinfunction "SHIELD_P3_3") (pintype "power_in"))
      (node (ref "USB2") (pin "P4_1") (pinfunction "SHIELD_P4_1") (pintype "power_in"))
      (node (ref "USB2") (pin "P4_2") (pinfunction "SHIELD_P4_2") (pintype "power_in"))
      (node (ref "USB2") (pin "P4_3") (pinfunction "SHIELD_P4_3") (pintype "power_in"))
      (node (ref "USB2") (pin "P5") (pinfunction "SHIELD_P5") (pintype "power_in"))
      (node (ref "USB2") (pin "P6") (pinfunction "SHIELD_P6") (pintype "power_in"))
    )
    (net (code "54") (name "Net-(1-Pad+)") (class "Default")
      (node (ref "1") (pin "+") (pinfunction "+_+") (pintype "passive"))
      (node (ref "R14") (pin "1") (pinfunction "1_1") (pintype "passive"))
    )
    (net (code "55") (name "Net-(2-Pad+)") (class "Default")
      (node (ref "2") (pin "+") (pinfunction "+_+") (pintype "passive"))
      (node (ref "R16") (pin "1") (pinfunction "1_1") (pintype "passive"))
    )
    (net (code "56") (name "Net-(3-Pad+)") (class "Default")
      (node (ref "3") (pin "+") (pinfunction "+_+") (pintype "passive"))
      (node (ref "R2") (pin "1") (pinfunction "1_1") (pintype "passive"))
    )
    (net (code "57") (name "Net-(4-Pad-)") (class "Default")
      (node (ref "4") (pin "-") (pinfunction "-_-") (pintype "passive"))
      (node (ref "R7") (pin "2") (pinfunction "2_2") (pintype "passive"))
    )
    (net (code "58") (name "Net-(ANT1-D)") (class "Default")
      (node (ref "ANT1") (pin "1") (pinfunction "D_1") (pintype "bidirectional"))
      (node (ref "C10") (pin "2") (pinfunction "2_2") (pintype "passive"))
      (node (ref "C9") (pin "2") (pinfunction "2_2") (pintype "passive"))
    )
    (net (code "59") (name "Net-(C5-Pad1)") (class "Default")
      (node (ref "C5") (pin "1") (pinfunction "1_1") (pintype "passive"))
      (node (ref "L2") (pin "P$2") (pinfunction "P$2_P$2") (pintype "passive"))
    )
    (net (code "60") (name "Net-(C11-Pad2)") (class "Default")
      (node (ref "C11") (pin "2") (pinfunction "2_2") (pintype "passive"))
      (node (ref "C5") (pin "2") (pinfunction "2_2") (pintype "passive"))
      (node (ref "C9") (pin "1") (pinfunction "1_1") (pintype "passive"))
    )
    (net (code "61") (name "Net-(C35-Pad2)") (class "Default")
      (node (ref "C35") (pin "2") (pinfunction "2_2") (pintype "passive"))
      (node (ref "R42") (pin "2") (pinfunction "2_2") (pintype "passive"))
      (node (ref "R43") (pin "1") (pinfunction "1_1") (pintype "passive"))
    )
    (net (code "62") (name "Net-(J8-CT)") (class "Default")
      (node (ref "C34") (pin "2") (pinfunction "2_2") (pintype "passive"))
      (node (ref "J8") (pin "2") (pinfunction "CT_2") (pintype "passive"))
      (node (ref "L4") (pin "1") (pinfunction "1_1") (pintype "passive"))
      (node (ref "R44") (pin "2") (pinfunction "2_2") (pintype "passive"))
      (node (ref "R45") (pin "1") (pinfunction "1_1") (pintype "passive"))
    )
    (net (code "63") (name "Net-(Q1-D)") (class "Default")
      (node (ref "Q1") (pin "3") (pinfunction "D_3") (pintype "passive"))
      (node (ref "R23") (pin "1") (pinfunction "1_1") (pintype "passive"))
      (node (ref "R24") (pin "2") (pinfunction "2_2") (pintype "passive"))
    )
    (net (code "64") (name "Net-(Q2-B)") (class "Default")
      (node (ref "Q2") (pin "1") (pinfunction "B_1") (pintype "passive"))
      (node (ref "R1") (pin "2") (pinfunction "2_2") (pintype "passive"))
    )
    (net (code "65") (name "Net-(Q3-B)") (class "Default")
      (node (ref "Q3") (pin "1") (pinfunction "B_1") (pintype "passive"))
      (node (ref "R3") (pin "2") (pinfunction "2_2") (pintype "passive"))
    )
    (net (code "66") (name "Net-(Q5-D)") (class "Default")
      (node (ref "C26") (pin "2") (pinfunction "2_2") (pintype "passive"))
      (node (ref "Q5") (pin "3") (pinfunction "D_3") (pintype "passive"))
      (node (ref "U9") (pin "F") (pinfunction "RH2_RED_F") (pintype "bidirectional"))
      (node (ref "U9") (pin "G") (pinfunction "RS2_RED_G") (pintype "bidirectional"))
      (node (ref "U9") (pin "H") (pinfunction "RH2_OX_H") (pintype "bidirectional"))
      (node (ref "U9") (pin "J") (pinfunction "RS2_OX_J") (pintype "bidirectional"))
    )
    (net (code "67") (name "Net-(R37-Pad2)") (class "Default")
      (node (ref "R37") (pin "2") (pinfunction "2_2") (pintype "passive"))
      (node (ref "U6") (pin "TXD") (pinfunction "TXD_TXD") (pintype "bidirectional"))
    )
    (net (code "68") (name "Net-(U2-TXD)") (class "Default")
      (node (ref "R34") (pin "2") (pinfunction "2_2") (pintype "passive"))
      (node (ref "U2") (pin "3") (pinfunction "TXD_3") (pintype "output"))
    )
    (net (code "69") (name "Net-(U2-UD+)") (class "Default")
      (node (ref "U2") (pin "6") (pinfunction "UD+_6") (pintype "bidirectional"))
      (node (ref "USB1") (pin "3") (pinfunction "D+_3") (pintype "bidirectional"))
    )
    (net (code "70") (name "Net-(U2-UD-)") (class "Default")
      (node (ref "U2") (pin "7") (pinfunction "UD-_7") (pintype "bidirectional"))
      (node (ref "USB1") (pin "2") (pinfunction "D-_2") (pintype "bidirectional"))
    )
    (net (code "71") (name "Net-(U2-XI)") (class "Default")
      (node (ref "C18") (pin "2") (pinfunction "2_2") (pintype "passive"))
      (node (ref "U2") (pin "9") (pinfunction "XI_9") (pintype "input"))
      (node (ref "Y1") (pin "2") (pinfunction "2_2") (pintype "passive"))
    )
    (net (code "72") (name "Net-(U2-XO)") (class "Default")
      (node (ref "C19") (pin "2") (pinfunction "2_2") (pintype "passive"))
      (node (ref "U2") (pin "10") (pinfunction "XO_10") (pintype "output"))
      (node (ref "Y1") (pin "1") (pinfunction "1_1") (pintype "passive"))
    )
    (net (code "73") (name "Net-(U4-RFIN)") (class "Default")
      (node (ref "L1") (pin "2") (pinfunction "2_2") (pintype "passive"))
      (node (ref "L2") (pin "P$1") (pinfunction "P$1_P$1") (pintype "passive"))
      (node (ref "U4") (pin "3") (pinfunction "RFIN_3") (pintype "bidirectional"))
    )
    (net (code "74") (name "Net-(U4-VCC)") (class "Default")
      (node (ref "C12") (pin "2") (pinfunction "2_2") (pintype "passive"))
      (node (ref "C15") (pin "2") (pinfunction "2_2") (pintype "passive"))
      (node (ref "R5") (pin "2") (pinfunction "2_2") (pintype "passive"))
      (node (ref "U4") (pin "4") (pinfunction "VCC_4") (pintype "power_in"))
    )
    (net (code "75") (name "Net-(U4-~{SHDN})") (class "Default")
      (node (ref "R6") (pin "2") (pinfunction "2_2") (pintype "passive"))
      (node (ref "U4") (pin "5") (pinfunction "~{SHDN}_5") (pintype "bidirectional"))
    )
    (net (code "76") (name "Net-(U5-RESERVED)") (class "Default")
      (node (ref "R18") (pin "2") (pinfunction "2_2") (pintype "passive"))
      (node (ref "U5") (pin "16") (pinfunction "RESERVED_16") (pintype "bidirectional"))
    )
    (net (code "77") (name "Net-(U5-RESERVED1)") (class "Default")
      (node (ref "R19") (pin "2") (pinfunction "2_2") (pintype "passive"))
      (node (ref "U5") (pin "17") (pinfunction "RESERVED1_17") (pintype "bidirectional"))
    )
    (net (code "78") (name "Net-(U5-RXD1)") (class "Default")
      (node (ref "R25") (pin "1") (pinfunction "1_1") (pintype "passive"))
      (node (ref "U5") (pin "3") (pinfunction "RXD1_3") (pintype "bidirectional"))
    )
    (net (code "79") (name "Net-(U5-TXD1)") (class "Default")
      (node (ref "R38") (pin "1") (pinfunction "1_1") (pintype "passive"))
      (node (ref "U5") (pin "2") (pinfunction "TXD1_2") (pintype "bidirectional"))
    )
    (net (code "80") (name "Net-(U5-V_BCKP)") (class "Default")
      (node (ref "BAT1") (pin "+1") (pinfunction "V+_+1") (pintype "bidirectional"))
      (node (ref "BAT1") (pin "+2") (pinfunction "V+_+2") (pintype "bidirectional"))
      (node (ref "U5") (pin "6") (pinfunction "V_BCKP_6") (pintype "bidirectional"))
    )
    (net (code "81") (name "Net-(U7-TXD0)") (class "Default")
      (node (ref "R33") (pin "2") (pinfunction "2_2") (pintype "passive"))
      (node (ref "U7") (pin "35") (pinfunction "TXD0_35") (pintype "output"))
    )
    (net (code "82") (name "Net-(U9-RH1_OX)") (class "Default")
      (node (ref "R23") (pin "2") (pinfunction "2_2") (pintype "passive"))
      (node (ref "U9") (pin "A") (pinfunction "RH1_OX_A") (pintype "bidirectional"))
    )
    (net (code "83") (name "Net-(U9-RH1_RED)") (class "Default")
      (node (ref "R21") (pin "2") (pinfunction "2_2") (pintype "passive"))
      (node (ref "U9") (pin "C") (pinfunction "RH1_RED_C") (pintype "bidirectional"))
    )
    (net (code "84") (name "Net-(U10-LEDA)") (class "Default")
      (node (ref "R39") (pin "1") (pinfunction "1_1") (pintype "passive"))
      (node (ref "U10") (pin "27") (pinfunction "LEDA_27") (pintype "output"))
    )
    (net (code "85") (name "Net-(U10-LEDB)") (class "Default")
      (node (ref "R40") (pin "1") (pinfunction "1_1") (pintype "passive"))
      (node (ref "U10") (pin "26") (pinfunction "LEDB_26") (pintype "output"))
    )
    (net (code "86") (name "unconnected-(SD1-CDN-Pad9)") (class "Default")
      (node (ref "SD1") (pin "9") (pinfunction "CDN_9") (pintype "bidirectional"))
    )
    (net (code "87") (name "unconnected-(SD1-DATA1-Pad8)") (class "Default")
      (node (ref "SD1") (pin "8") (pinfunction "DATA1_8") (pintype "bidirectional"))
    )
    (net (code "88") (name "unconnected-(SD1-DATA2-Pad1)") (class "Default")
      (node (ref "SD1") (pin "1") (pinfunction "DATA2_1") (pintype "bidirectional"))
    )
    (net (code "89") (name "unconnected-(U$22-ST-Pad1)") (class "Default")
      (node (ref "U$22") (pin "1") (pinfunction "ST_1") (pintype "bidirectional"))
    )
    (net (code "90") (name "unconnected-(U2-ACT#-Pad2)") (class "Default")
      (node (ref "U2") (pin "2") (pinfunction "ACT#_2") (pintype "output"))
    )
    (net (code "91") (name "unconnected-(U2-CKO-Pad1)") (class "Default")
      (node (ref "U2") (pin "1") (pinfunction "CKO_1") (pintype "output"))
    )
    (net (code "92") (name "unconnected-(U2-CTS#-Pad11)") (class "Default")
      (node (ref "U2") (pin "11") (pinfunction "CTS#_11") (pintype "input"))
    )
    (net (code "93") (name "unconnected-(U2-DCD#-Pad14)") (class "Default")
      (node (ref "U2") (pin "14") (pinfunction "DCD#_14") (pintype "input"))
    )
    (net (code "94") (name "unconnected-(U2-DSR#-Pad12)") (class "Default")
      (node (ref "U2") (pin "12") (pinfunction "DSR#_12") (pintype "input"))
    )
    (net (code "95") (name "unconnected-(U2-NC-Pad17)") (class "Default")
      (node (ref "U2") (pin "17") (pinfunction "NC_17") (pintype "no_connect"))
    )
    (net (code "96") (name "unconnected-(U2-R232-Pad18)") (class "Default")
      (node (ref "U2") (pin "18") (pinfunction "R232_18") (pintype "input"))
    )
    (net (code "97") (name "unconnected-(U2-RI#-Pad13)") (class "Default")
      (node (ref "U2") (pin "13") (pinfunction "RI#_13") (pintype "input"))
    )
    (net (code "98") (name "unconnected-(U5-NC-Pad7)") (class "Default")
      (node (ref "U5") (pin "7") (pinfunction "NC_7") (pintype "bidirectional"))
    )
    (net (code "99") (name "unconnected-(U5-NC-Pad15)") (class "Default")
      (node (ref "U5") (pin "15") (pinfunction "NC_15") (pintype "bidirectional"))
    )
    (net (code "100") (name "unconnected-(U5-STANDBY-Pad5)") (class "Default")
      (node (ref "U5") (pin "5") (pinfunction "STANDBY_5") (pintype "bidirectional"))
    )
    (net (code "101") (name "unconnected-(U5-TIMER-Pad18)") (class "Default")
      (node (ref "U5") (pin "18") (pinfunction "TIMER_18") (pintype "bidirectional"))
    )
    (net (code "102") (name "unconnected-(U6-PadRXD)") (class "Default")
      (node (ref "U6") (pin "RXD") (pinfunction "RXD_RXD") (pintype "bidirectional"))
    )
    (net (code "103") (name "unconnected-(U7-CLK-Pad20)") (class "Default")
      (node (ref "U7") (pin "20") (pinfunction "CLK_20") (pintype "bidirectional"))
    )
    (net (code "104") (name "unconnected-(U7-CMD-Pad19)") (class "Default")
      (node (ref "U7") (pin "19") (pinfunction "CMD_19") (pintype "bidirectional"))
    )
    (net (code "105") (name "unconnected-(U7-IO17-Pad28)") (class "Default")
      (node (ref "U7") (pin "28") (pinfunction "IO17_28") (pintype "bidirectional"))
    )
    (net (code "106") (name "unconnected-(U7-SD0-Pad21)") (class "Default")
      (node (ref "U7") (pin "21") (pinfunction "SD0_21") (pintype "bidirectional"))
    )
    (net (code "107") (name "unconnected-(U7-SD1-Pad22)") (class "Default")
      (node (ref "U7") (pin "22") (pinfunction "SD1_22") (pintype "bidirectional"))
    )
    (net (code "108") (name "unconnected-(U7-SD2-Pad17)") (class "Default")
      (node (ref "U7") (pin "17") (pinfunction "SD2_17") (pintype "bidirectional"))
    )
    (net (code "109") (name "unconnected-(U7-SD3-Pad18)") (class "Default")
      (node (ref "U7") (pin "18") (pinfunction "SD3_18") (pintype "bidirectional"))
    )
    (net (code "110") (name "unconnected-(U10-CLKOUT-Pad3)") (class "Default")
      (node (ref "U10") (pin "3") (pinfunction "CLKOUT_3") (pintype "output"))
    )
    (net (code "111") (name "unconnected-(U10-NC*-Pad5)") (class "Default")
      (node (ref "U10") (pin "5") (pinfunction "NC*_5") (pintype "output"))
    )
    (net (code "112") (name "unconnected-(U10-~{RESET}-Pad10)") (class "Default")
      (node (ref "U10") (pin "10") (pinfunction "~{RESET}_10") (pintype "input"))
    )
    (net (code "113") (name "unconnected-(U13-ADJ-Pad4)") (class "Default")
      (node (ref "U13") (pin "4") (pinfunction "ADJ_4") (pintype "bidirectional"))
    )
    (net (code "114") (name "unconnected-(USB1-ID-Pad4)") (class "Default")
      (node (ref "USB1") (pin "4") (pinfunction "ID_4") (pintype "bidirectional"))
    )
    (net (code "115") (name "unconnected-(USB2-D+-Pad3)") (class "Default")
      (node (ref "USB2") (pin "3") (pinfunction "D+_3") (pintype "bidirectional"))
    )
    (net (code "116") (name "unconnected-(USB2-D--Pad2)") (class "Default")
      (node (ref "USB2") (pin "2") (pinfunction "D-_2") (pintype "bidirectional"))
    )
    (net (code "117") (name "unconnected-(USB2-ID-Pad4)") (class "Default")
      (node (ref "USB2") (pin "4") (pinfunction "ID_4") (pintype "bidirectional"))
    )
  )
)
